# Galaksija_keyboard_matrix.net
KiCad netlist of a schematic drawn in EAGLE
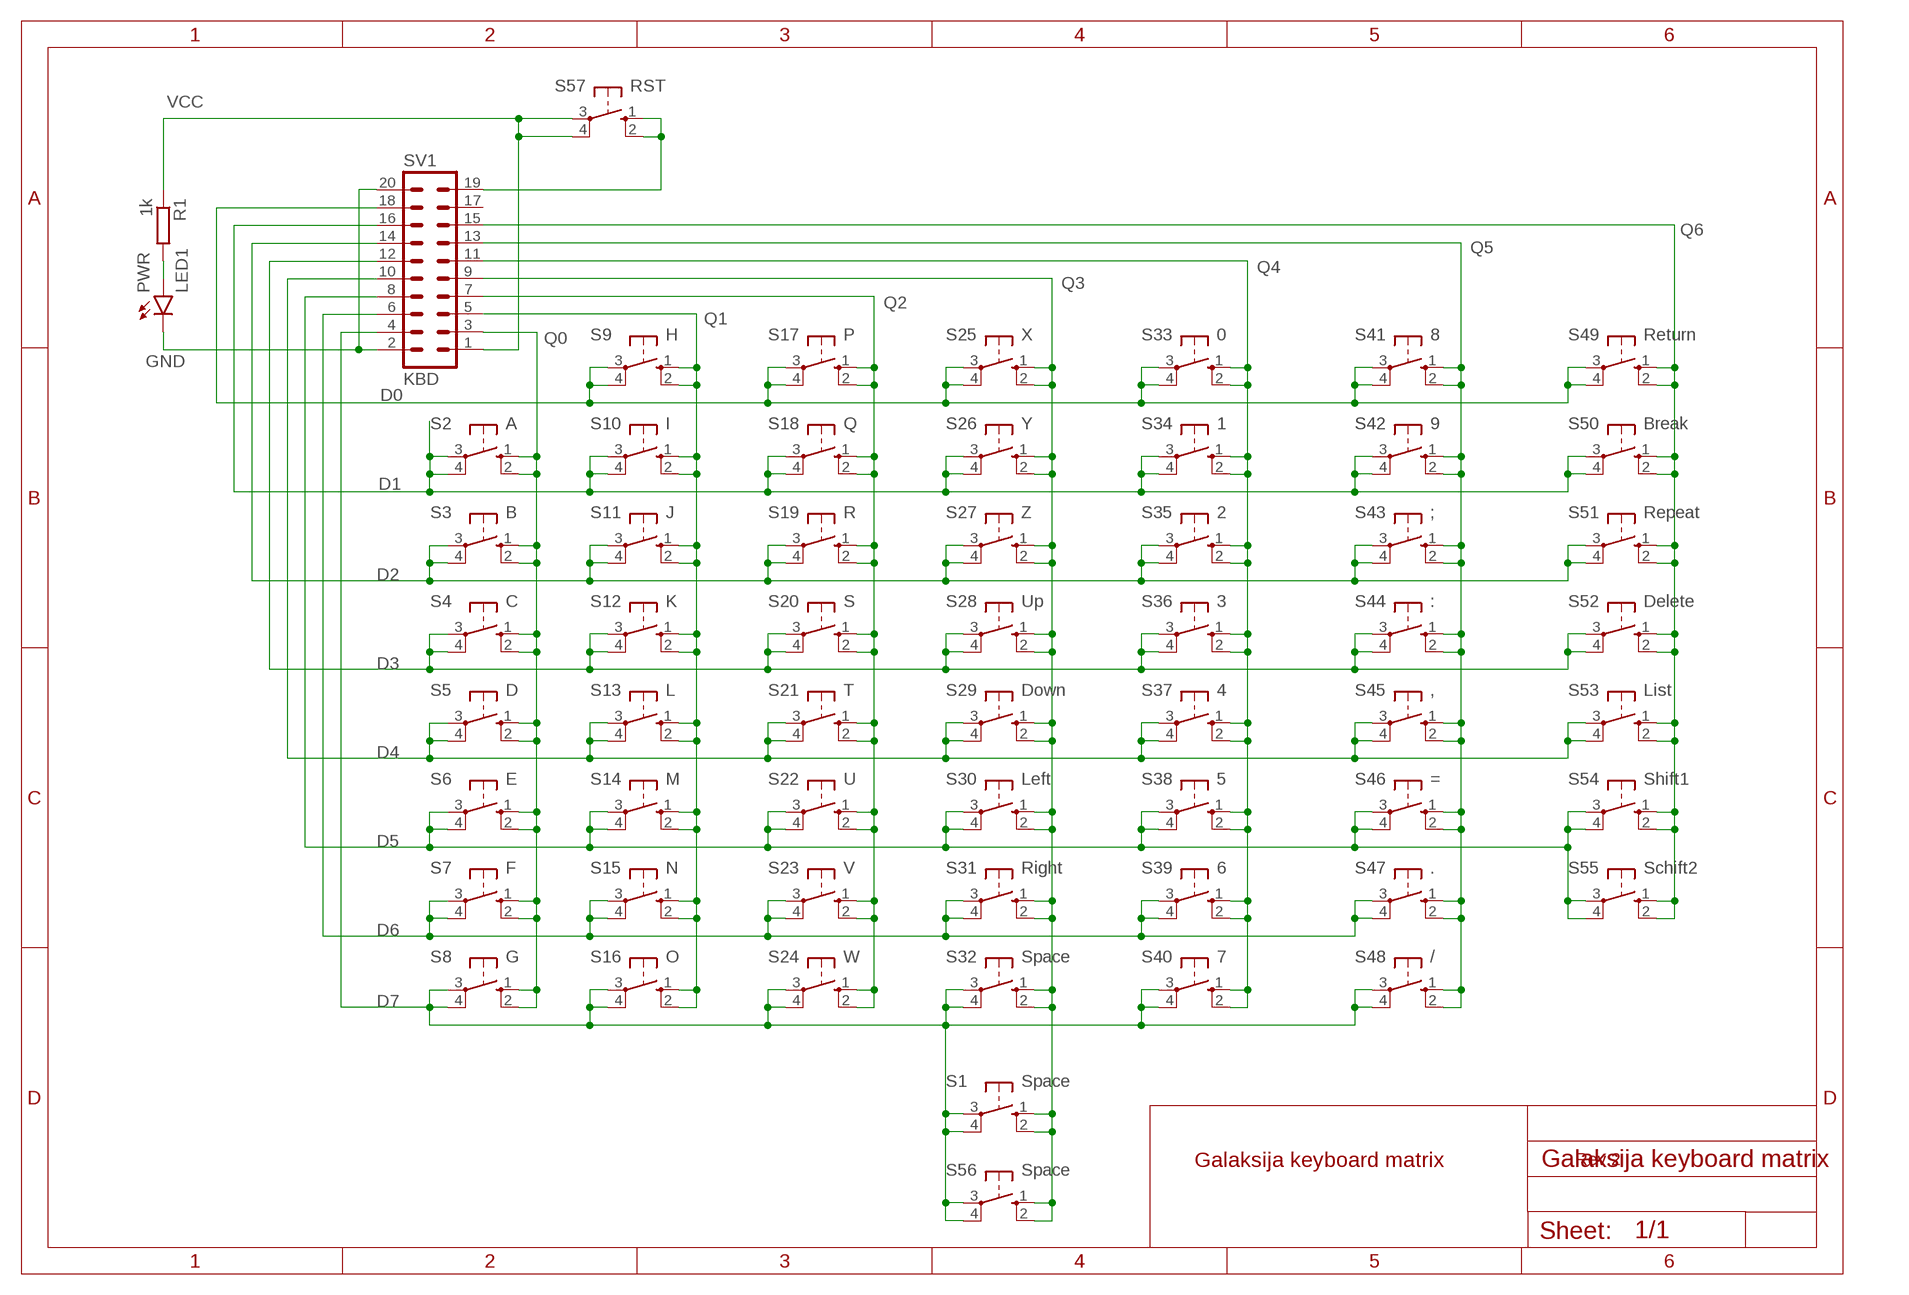
[diagram p0: schematic, sheet 1]

(export (version "E")
  (design (tool "Eeschema 10.0.6"))
  (components
    (comp (ref "LED1")
      (value "PWR")
      (footprint "eagle-import:LED5MM")
      (libsource (lib "eagle-import") (part "LED5MM"))
    )
    (comp (ref "R1")
      (value "1k")
      (footprint "eagle-import:0207_10")
      (libsource (lib "eagle-import") (part "R-EU_0207/10"))
    )
    (comp (ref "S1")
      (value "Space")
      (footprint "eagle-import:B3F-40XX")
      (fields (field (name "MF") "OMRON COMPONENTS USA") (field (name "MPN") "B3F-4000"))
      (libsource (lib "eagle-import") (part "40-XX"))
    )
    (comp (ref "S2")
      (value "A")
      (footprint "eagle-import:B3F-40XX")
      (fields (field (name "MF") "OMRON COMPONENTS USA") (field (name "MPN") "B3F-4000"))
      (libsource (lib "eagle-import") (part "40-XX"))
    )
    (comp (ref "S3")
      (value "B")
      (footprint "eagle-import:B3F-40XX")
      (fields (field (name "MF") "OMRON COMPONENTS USA") (field (name "MPN") "B3F-4000"))
      (libsource (lib "eagle-import") (part "40-XX"))
    )
    (comp (ref "S4")
      (value "C")
      (footprint "eagle-import:B3F-40XX")
      (fields (field (name "MF") "OMRON COMPONENTS USA") (field (name "MPN") "B3F-4000"))
      (libsource (lib "eagle-import") (part "40-XX"))
    )
    (comp (ref "S5")
      (value "D")
      (footprint "eagle-import:B3F-40XX")
      (fields (field (name "MF") "OMRON COMPONENTS USA") (field (name "MPN") "B3F-4000"))
      (libsource (lib "eagle-import") (part "40-XX"))
    )
    (comp (ref "S6")
      (value "E")
      (footprint "eagle-import:B3F-40XX")
      (fields (field (name "MF") "OMRON COMPONENTS USA") (field (name "MPN") "B3F-4000"))
      (libsource (lib "eagle-import") (part "40-XX"))
    )
    (comp (ref "S7")
      (value "F")
      (footprint "eagle-import:B3F-40XX")
      (fields (field (name "MF") "OMRON COMPONENTS USA") (field (name "MPN") "B3F-4000"))
      (libsource (lib "eagle-import") (part "40-XX"))
    )
    (comp (ref "S8")
      (value "G")
      (footprint "eagle-import:B3F-40XX")
      (fields (field (name "MF") "OMRON COMPONENTS USA") (field (name "MPN") "B3F-4000"))
      (libsource (lib "eagle-import") (part "40-XX"))
    )
    (comp (ref "S9")
      (value "H")
      (footprint "eagle-import:B3F-40XX")
      (fields (field (name "MF") "OMRON COMPONENTS USA") (field (name "MPN") "B3F-4000"))
      (libsource (lib "eagle-import") (part "40-XX"))
    )
    (comp (ref "S10")
      (value "I")
      (footprint "eagle-import:B3F-40XX")
      (fields (field (name "MF") "OMRON COMPONENTS USA") (field (name "MPN") "B3F-4000"))
      (libsource (lib "eagle-import") (part "40-XX"))
    )
    (comp (ref "S11")
      (value "J")
      (footprint "eagle-import:B3F-40XX")
      (fields (field (name "MF") "OMRON COMPONENTS USA") (field (name "MPN") "B3F-4000"))
      (libsource (lib "eagle-import") (part "40-XX"))
    )
    (comp (ref "S12")
      (value "K")
      (footprint "eagle-import:B3F-40XX")
      (fields (field (name "MF") "OMRON COMPONENTS USA") (field (name "MPN") "B3F-4000"))
      (libsource (lib "eagle-import") (part "40-XX"))
    )
    (comp (ref "S13")
      (value "L")
      (footprint "eagle-import:B3F-40XX")
      (fields (field (name "MF") "OMRON COMPONENTS USA") (field (name "MPN") "B3F-4000"))
      (libsource (lib "eagle-import") (part "40-XX"))
    )
    (comp (ref "S14")
      (value "M")
      (footprint "eagle-import:B3F-40XX")
      (fields (field (name "MF") "OMRON COMPONENTS USA") (field (name "MPN") "B3F-4000"))
      (libsource (lib "eagle-import") (part "40-XX"))
    )
    (comp (ref "S15")
      (value "N")
      (footprint "eagle-import:B3F-40XX")
      (fields (field (name "MF") "OMRON COMPONENTS USA") (field (name "MPN") "B3F-4000"))
      (libsource (lib "eagle-import") (part "40-XX"))
    )
    (comp (ref "S16")
      (value "O")
      (footprint "eagle-import:B3F-40XX")
      (fields (field (name "MF") "OMRON COMPONENTS USA") (field (name "MPN") "B3F-4000"))
      (libsource (lib "eagle-import") (part "40-XX"))
    )
    (comp (ref "S17")
      (value "P")
      (footprint "eagle-import:B3F-40XX")
      (fields (field (name "MF") "OMRON COMPONENTS USA") (field (name "MPN") "B3F-4000"))
      (libsource (lib "eagle-import") (part "40-XX"))
    )
    (comp (ref "S18")
      (value "Q")
      (footprint "eagle-import:B3F-40XX")
      (fields (field (name "MF") "OMRON COMPONENTS USA") (field (name "MPN") "B3F-4000"))
      (libsource (lib "eagle-import") (part "40-XX"))
    )
    (comp (ref "S19")
      (value "R")
      (footprint "eagle-import:B3F-40XX")
      (fields (field (name "MF") "OMRON COMPONENTS USA") (field (name "MPN") "B3F-4000"))
      (libsource (lib "eagle-import") (part "40-XX"))
    )
    (comp (ref "S20")
      (value "S")
      (footprint "eagle-import:B3F-40XX")
      (fields (field (name "MF") "OMRON COMPONENTS USA") (field (name "MPN") "B3F-4000"))
      (libsource (lib "eagle-import") (part "40-XX"))
    )
    (comp (ref "S21")
      (value "T")
      (footprint "eagle-import:B3F-40XX")
      (fields (field (name "MF") "OMRON COMPONENTS USA") (field (name "MPN") "B3F-4000"))
      (libsource (lib "eagle-import") (part "40-XX"))
    )
    (comp (ref "S22")
      (value "U")
      (footprint "eagle-import:B3F-40XX")
      (fields (field (name "MF") "OMRON COMPONENTS USA") (field (name "MPN") "B3F-4000"))
      (libsource (lib "eagle-import") (part "40-XX"))
    )
    (comp (ref "S23")
      (value "V")
      (footprint "eagle-import:B3F-40XX")
      (fields (field (name "MF") "OMRON COMPONENTS USA") (field (name "MPN") "B3F-4000"))
      (libsource (lib "eagle-import") (part "40-XX"))
    )
    (comp (ref "S24")
      (value "W")
      (footprint "eagle-import:B3F-40XX")
      (fields (field (name "MF") "OMRON COMPONENTS USA") (field (name "MPN") "B3F-4000"))
      (libsource (lib "eagle-import") (part "40-XX"))
    )
    (comp (ref "S25")
      (value "X")
      (footprint "eagle-import:B3F-40XX")
      (fields (field (name "MF") "OMRON COMPONENTS USA") (field (name "MPN") "B3F-4000"))
      (libsource (lib "eagle-import") (part "40-XX"))
    )
    (comp (ref "S26")
      (value "Y")
      (footprint "eagle-import:B3F-40XX")
      (fields (field (name "MF") "OMRON COMPONENTS USA") (field (name "MPN") "B3F-4000"))
      (libsource (lib "eagle-import") (part "40-XX"))
    )
    (comp (ref "S27")
      (value "Z")
      (footprint "eagle-import:B3F-40XX")
      (fields (field (name "MF") "OMRON COMPONENTS USA") (field (name "MPN") "B3F-4000"))
      (libsource (lib "eagle-import") (part "40-XX"))
    )
    (comp (ref "S28")
      (value "Up")
      (footprint "eagle-import:B3F-40XX")
      (fields (field (name "MF") "OMRON COMPONENTS USA") (field (name "MPN") "B3F-4000"))
      (libsource (lib "eagle-import") (part "40-XX"))
    )
    (comp (ref "S29")
      (value "Down")
      (footprint "eagle-import:B3F-40XX")
      (fields (field (name "MF") "OMRON COMPONENTS USA") (field (name "MPN") "B3F-4000"))
      (libsource (lib "eagle-import") (part "40-XX"))
    )
    (comp (ref "S30")
      (value "Left")
      (footprint "eagle-import:B3F-40XX")
      (fields (field (name "MF") "OMRON COMPONENTS USA") (field (name "MPN") "B3F-4000"))
      (libsource (lib "eagle-import") (part "40-XX"))
    )
    (comp (ref "S31")
      (value "Right")
      (footprint "eagle-import:B3F-40XX")
      (fields (field (name "MF") "OMRON COMPONENTS USA") (field (name "MPN") "B3F-4000"))
      (libsource (lib "eagle-import") (part "40-XX"))
    )
    (comp (ref "S32")
      (value "Space")
      (footprint "eagle-import:B3F-40XX")
      (fields (field (name "MF") "OMRON COMPONENTS USA") (field (name "MPN") "B3F-4000"))
      (libsource (lib "eagle-import") (part "40-XX"))
    )
    (comp (ref "S33")
      (value "0")
      (footprint "eagle-import:B3F-40XX")
      (fields (field (name "MF") "OMRON COMPONENTS USA") (field (name "MPN") "B3F-4000"))
      (libsource (lib "eagle-import") (part "40-XX"))
    )
    (comp (ref "S34")
      (value "1")
      (footprint "eagle-import:B3F-40XX")
      (fields (field (name "MF") "OMRON COMPONENTS USA") (field (name "MPN") "B3F-4000"))
      (libsource (lib "eagle-import") (part "40-XX"))
    )
    (comp (ref "S35")
      (value "2")
      (footprint "eagle-import:B3F-40XX")
      (fields (field (name "MF") "OMRON COMPONENTS USA") (field (name "MPN") "B3F-4000"))
      (libsource (lib "eagle-import") (part "40-XX"))
    )
    (comp (ref "S36")
      (value "3")
      (footprint "eagle-import:B3F-40XX")
      (fields (field (name "MF") "OMRON COMPONENTS USA") (field (name "MPN") "B3F-4000"))
      (libsource (lib "eagle-import") (part "40-XX"))
    )
    (comp (ref "S37")
      (value "4")
      (footprint "eagle-import:B3F-40XX")
      (fields (field (name "MF") "OMRON COMPONENTS USA") (field (name "MPN") "B3F-4000"))
      (libsource (lib "eagle-import") (part "40-XX"))
    )
    (comp (ref "S38")
      (value "5")
      (footprint "eagle-import:B3F-40XX")
      (fields (field (name "MF") "OMRON COMPONENTS USA") (field (name "MPN") "B3F-4000"))
      (libsource (lib "eagle-import") (part "40-XX"))
    )
    (comp (ref "S39")
      (value "6")
      (footprint "eagle-import:B3F-40XX")
      (fields (field (name "MF") "OMRON COMPONENTS USA") (field (name "MPN") "B3F-4000"))
      (libsource (lib "eagle-import") (part "40-XX"))
    )
    (comp (ref "S40")
      (value "7")
      (footprint "eagle-import:B3F-40XX")
      (fields (field (name "MF") "OMRON COMPONENTS USA") (field (name "MPN") "B3F-4000"))
      (libsource (lib "eagle-import") (part "40-XX"))
    )
    (comp (ref "S41")
      (value "8")
      (footprint "eagle-import:B3F-40XX")
      (fields (field (name "MF") "OMRON COMPONENTS USA") (field (name "MPN") "B3F-4000"))
      (libsource (lib "eagle-import") (part "40-XX"))
    )
    (comp (ref "S42")
      (value "9")
      (footprint "eagle-import:B3F-40XX")
      (fields (field (name "MF") "OMRON COMPONENTS USA") (field (name "MPN") "B3F-4000"))
      (libsource (lib "eagle-import") (part "40-XX"))
    )
    (comp (ref "S43")
      (value ";")
      (footprint "eagle-import:B3F-40XX")
      (fields (field (name "MF") "OMRON COMPONENTS USA") (field (name "MPN") "B3F-4000"))
      (libsource (lib "eagle-import") (part "40-XX"))
    )
    (comp (ref "S44")
      (value ":")
      (footprint "eagle-import:B3F-40XX")
      (fields (field (name "MF") "OMRON COMPONENTS USA") (field (name "MPN") "B3F-4000"))
      (libsource (lib "eagle-import") (part "40-XX"))
    )
    (comp (ref "S45")
      (value ",")
      (footprint "eagle-import:B3F-40XX")
      (fields (field (name "MF") "OMRON COMPONENTS USA") (field (name "MPN") "B3F-4000"))
      (libsource (lib "eagle-import") (part "40-XX"))
    )
    (comp (ref "S46")
      (value "=")
      (footprint "eagle-import:B3F-40XX")
      (fields (field (name "MF") "OMRON COMPONENTS USA") (field (name "MPN") "B3F-4000"))
      (libsource (lib "eagle-import") (part "40-XX"))
    )
    (comp (ref "S47")
      (value ".")
      (footprint "eagle-import:B3F-40XX")
      (fields (field (name "MF") "OMRON COMPONENTS USA") (field (name "MPN") "B3F-4000"))
      (libsource (lib "eagle-import") (part "40-XX"))
    )
    (comp (ref "S48")
      (value "/")
      (footprint "eagle-import:B3F-40XX")
      (fields (field (name "MF") "OMRON COMPONENTS USA") (field (name "MPN") "B3F-4000"))
      (libsource (lib "eagle-import") (part "40-XX"))
    )
    (comp (ref "S49")
      (value "Return")
      (footprint "eagle-import:B3F-40XX")
      (fields (field (name "MF") "OMRON COMPONENTS USA") (field (name "MPN") "B3F-4000"))
      (libsource (lib "eagle-import") (part "40-XX"))
    )
    (comp (ref "S50")
      (value "Break")
      (footprint "eagle-import:B3F-40XX")
      (fields (field (name "MF") "OMRON COMPONENTS USA") (field (name "MPN") "B3F-4000"))
      (libsource (lib "eagle-import") (part "40-XX"))
    )
    (comp (ref "S51")
      (value "Repeat")
      (footprint "eagle-import:B3F-40XX")
      (fields (field (name "MF") "OMRON COMPONENTS USA") (field (name "MPN") "B3F-4000"))
      (libsource (lib "eagle-import") (part "40-XX"))
    )
    (comp (ref "S52")
      (value "Delete")
      (footprint "eagle-import:B3F-40XX")
      (fields (field (name "MF") "OMRON COMPONENTS USA") (field (name "MPN") "B3F-4000"))
      (libsource (lib "eagle-import") (part "40-XX"))
    )
    (comp (ref "S53")
      (value "List")
      (footprint "eagle-import:B3F-40XX")
      (fields (field (name "MF") "OMRON COMPONENTS USA") (field (name "MPN") "B3F-4000"))
      (libsource (lib "eagle-import") (part "40-XX"))
    )
    (comp (ref "S54")
      (value "Shift1")
      (footprint "eagle-import:B3F-40XX")
      (fields (field (name "MF") "OMRON COMPONENTS USA") (field (name "MPN") "B3F-4000"))
      (libsource (lib "eagle-import") (part "40-XX"))
    )
    (comp (ref "S55")
      (value "Schift2")
      (footprint "eagle-import:B3F-40XX")
      (fields (field (name "MF") "OMRON COMPONENTS USA") (field (name "MPN") "B3F-4000"))
      (libsource (lib "eagle-import") (part "40-XX"))
    )
    (comp (ref "S56")
      (value "Space")
      (footprint "eagle-import:B3F-40XX")
      (fields (field (name "MF") "OMRON COMPONENTS USA") (field (name "MPN") "B3F-4000"))
      (libsource (lib "eagle-import") (part "40-XX"))
    )
    (comp (ref "S57")
      (value "RST")
      (footprint "eagle-import:B3F-40XX")
      (fields (field (name "MF") "OMRON COMPONENTS USA") (field (name "MPN") "B3F-4000"))
      (libsource (lib "eagle-import") (part "40-XX"))
    )
    (comp (ref "SV1")
      (value "KBD")
      (footprint "eagle-import:ML20")
      (libsource (lib "eagle-import") (part "ML20"))
    )
  )
  (nets
    (net (code "1") (name "/D0") (class "Default")
      (node (ref "S17") (pin "3") (pinfunction "P_3") (pintype "passive"))
      (node (ref "S17") (pin "4") (pinfunction "P1_4") (pintype "passive"))
      (node (ref "S25") (pin "3") (pinfunction "P_3") (pintype "passive"))
      (node (ref "S25") (pin "4") (pinfunction "P1_4") (pintype "passive"))
      (node (ref "S33") (pin "3") (pinfunction "P_3") (pintype "passive"))
      (node (ref "S33") (pin "4") (pinfunction "P1_4") (pintype "passive"))
      (node (ref "S41") (pin "3") (pinfunction "P_3") (pintype "passive"))
      (node (ref "S41") (pin "4") (pinfunction "P1_4") (pintype "passive"))
      (node (ref "S49") (pin "3") (pinfunction "P_3") (pintype "passive"))
      (node (ref "S49") (pin "4") (pinfunction "P1_4") (pintype "passive"))
      (node (ref "S9") (pin "3") (pinfunction "P_3") (pintype "passive"))
      (node (ref "S9") (pin "4") (pinfunction "P1_4") (pintype "passive"))
      (node (ref "SV1") (pin "18") (pinfunction "18_18") (pintype "passive"))
    )
    (net (code "2") (name "/D1") (class "Default")
      (node (ref "S10") (pin "3") (pinfunction "P_3") (pintype "passive"))
      (node (ref "S10") (pin "4") (pinfunction "P1_4") (pintype "passive"))
      (node (ref "S18") (pin "3") (pinfunction "P_3") (pintype "passive"))
      (node (ref "S18") (pin "4") (pinfunction "P1_4") (pintype "passive"))
      (node (ref "S2") (pin "3") (pinfunction "P_3") (pintype "passive"))
      (node (ref "S2") (pin "4") (pinfunction "P1_4") (pintype "passive"))
      (node (ref "S26") (pin "3") (pinfunction "P_3") (pintype "passive"))
      (node (ref "S26") (pin "4") (pinfunction "P1_4") (pintype "passive"))
      (node (ref "S34") (pin "3") (pinfunction "P_3") (pintype "passive"))
      (node (ref "S34") (pin "4") (pinfunction "P1_4") (pintype "passive"))
      (node (ref "S42") (pin "3") (pinfunction "P_3") (pintype "passive"))
      (node (ref "S42") (pin "4") (pinfunction "P1_4") (pintype "passive"))
      (node (ref "S50") (pin "3") (pinfunction "P_3") (pintype "passive"))
      (node (ref "S50") (pin "4") (pinfunction "P1_4") (pintype "passive"))
      (node (ref "SV1") (pin "16") (pinfunction "16_16") (pintype "passive"))
    )
    (net (code "3") (name "/D2") (class "Default")
      (node (ref "S11") (pin "3") (pinfunction "P_3") (pintype "passive"))
      (node (ref "S11") (pin "4") (pinfunction "P1_4") (pintype "passive"))
      (node (ref "S19") (pin "3") (pinfunction "P_3") (pintype "passive"))
      (node (ref "S19") (pin "4") (pinfunction "P1_4") (pintype "passive"))
      (node (ref "S27") (pin "3") (pinfunction "P_3") (pintype "passive"))
      (node (ref "S27") (pin "4") (pinfunction "P1_4") (pintype "passive"))
      (node (ref "S3") (pin "3") (pinfunction "P_3") (pintype "passive"))
      (node (ref "S3") (pin "4") (pinfunction "P1_4") (pintype "passive"))
      (node (ref "S35") (pin "3") (pinfunction "P_3") (pintype "passive"))
      (node (ref "S35") (pin "4") (pinfunction "P1_4") (pintype "passive"))
      (node (ref "S43") (pin "3") (pinfunction "P_3") (pintype "passive"))
      (node (ref "S43") (pin "4") (pinfunction "P1_4") (pintype "passive"))
      (node (ref "S51") (pin "3") (pinfunction "P_3") (pintype "passive"))
      (node (ref "S51") (pin "4") (pinfunction "P1_4") (pintype "passive"))
      (node (ref "SV1") (pin "14") (pinfunction "14_14") (pintype "passive"))
    )
    (net (code "4") (name "/D3") (class "Default")
      (node (ref "S12") (pin "3") (pinfunction "P_3") (pintype "passive"))
      (node (ref "S12") (pin "4") (pinfunction "P1_4") (pintype "passive"))
      (node (ref "S20") (pin "3") (pinfunction "P_3") (pintype "passive"))
      (node (ref "S20") (pin "4") (pinfunction "P1_4") (pintype "passive"))
      (node (ref "S28") (pin "3") (pinfunction "P_3") (pintype "passive"))
      (node (ref "S28") (pin "4") (pinfunction "P1_4") (pintype "passive"))
      (node (ref "S36") (pin "3") (pinfunction "P_3") (pintype "passive"))
      (node (ref "S36") (pin "4") (pinfunction "P1_4") (pintype "passive"))
      (node (ref "S4") (pin "3") (pinfunction "P_3") (pintype "passive"))
      (node (ref "S4") (pin "4") (pinfunction "P1_4") (pintype "passive"))
      (node (ref "S44") (pin "3") (pinfunction "P_3") (pintype "passive"))
      (node (ref "S44") (pin "4") (pinfunction "P1_4") (pintype "passive"))
      (node (ref "S52") (pin "3") (pinfunction "P_3") (pintype "passive"))
      (node (ref "S52") (pin "4") (pinfunction "P1_4") (pintype "passive"))
      (node (ref "SV1") (pin "12") (pinfunction "12_12") (pintype "passive"))
    )
    (net (code "5") (name "/D4") (class "Default")
      (node (ref "S13") (pin "3") (pinfunction "P_3") (pintype "passive"))
      (node (ref "S13") (pin "4") (pinfunction "P1_4") (pintype "passive"))
      (node (ref "S21") (pin "3") (pinfunction "P_3") (pintype "passive"))
      (node (ref "S21") (pin "4") (pinfunction "P1_4") (pintype "passive"))
      (node (ref "S29") (pin "3") (pinfunction "P_3") (pintype "passive"))
      (node (ref "S29") (pin "4") (pinfunction "P1_4") (pintype "passive"))
      (node (ref "S37") (pin "3") (pinfunction "P_3") (pintype "passive"))
      (node (ref "S37") (pin "4") (pinfunction "P1_4") (pintype "passive"))
      (node (ref "S45") (pin "3") (pinfunction "P_3") (pintype "passive"))
      (node (ref "S45") (pin "4") (pinfunction "P1_4") (pintype "passive"))
      (node (ref "S5") (pin "3") (pinfunction "P_3") (pintype "passive"))
      (node (ref "S5") (pin "4") (pinfunction "P1_4") (pintype "passive"))
      (node (ref "S53") (pin "3") (pinfunction "P_3") (pintype "passive"))
      (node (ref "S53") (pin "4") (pinfunction "P1_4") (pintype "passive"))
      (node (ref "SV1") (pin "10") (pinfunction "10_10") (pintype "passive"))
    )
    (net (code "6") (name "/D5") (class "Default")
      (node (ref "S14") (pin "3") (pinfunction "P_3") (pintype "passive"))
      (node (ref "S14") (pin "4") (pinfunction "P1_4") (pintype "passive"))
      (node (ref "S22") (pin "3") (pinfunction "P_3") (pintype "passive"))
      (node (ref "S22") (pin "4") (pinfunction "P1_4") (pintype "passive"))
      (node (ref "S30") (pin "3") (pinfunction "P_3") (pintype "passive"))
      (node (ref "S30") (pin "4") (pinfunction "P1_4") (pintype "passive"))
      (node (ref "S38") (pin "3") (pinfunction "P_3") (pintype "passive"))
      (node (ref "S38") (pin "4") (pinfunction "P1_4") (pintype "passive"))
      (node (ref "S46") (pin "3") (pinfunction "P_3") (pintype "passive"))
      (node (ref "S46") (pin "4") (pinfunction "P1_4") (pintype "passive"))
      (node (ref "S54") (pin "3") (pinfunction "P_3") (pintype "passive"))
      (node (ref "S54") (pin "4") (pinfunction "P1_4") (pintype "passive"))
      (node (ref "S55") (pin "3") (pinfunction "P_3") (pintype "passive"))
      (node (ref "S55") (pin "4") (pinfunction "P1_4") (pintype "passive"))
      (node (ref "S6") (pin "3") (pinfunction "P_3") (pintype "passive"))
      (node (ref "S6") (pin "4") (pinfunction "P1_4") (pintype "passive"))
      (node (ref "SV1") (pin "8") (pinfunction "8_8") (pintype "passive"))
    )
    (net (code "7") (name "/D6") (class "Default")
      (node (ref "S15") (pin "3") (pinfunction "P_3") (pintype "passive"))
      (node (ref "S15") (pin "4") (pinfunction "P1_4") (pintype "passive"))
      (node (ref "S23") (pin "3") (pinfunction "P_3") (pintype "passive"))
      (node (ref "S23") (pin "4") (pinfunction "P1_4") (pintype "passive"))
      (node (ref "S31") (pin "3") (pinfunction "P_3") (pintype "passive"))
      (node (ref "S31") (pin "4") (pinfunction "P1_4") (pintype "passive"))
      (node (ref "S39") (pin "3") (pinfunction "P_3") (pintype "passive"))
      (node (ref "S39") (pin "4") (pinfunction "P1_4") (pintype "passive"))
      (node (ref "S47") (pin "3") (pinfunction "P_3") (pintype "passive"))
      (node (ref "S47") (pin "4") (pinfunction "P1_4") (pintype "passive"))
      (node (ref "S7") (pin "3") (pinfunction "P_3") (pintype "passive"))
      (node (ref "S7") (pin "4") (pinfunction "P1_4") (pintype "passive"))
      (node (ref "SV1") (pin "6") (pinfunction "6_6") (pintype "passive"))
    )
    (net (code "8") (name "/D7") (class "Default")
      (node (ref "S1") (pin "3") (pinfunction "P_3") (pintype "passive"))
      (node (ref "S1") (pin "4") (pinfunction "P1_4") (pintype "passive"))
      (node (ref "S16") (pin "3") (pinfunction "P_3") (pintype "passive"))
      (node (ref "S16") (pin "4") (pinfunction "P1_4") (pintype "passive"))
      (node (ref "S24") (pin "3") (pinfunction "P_3") (pintype "passive"))
      (node (ref "S24") (pin "4") (pinfunction "P1_4") (pintype "passive"))
      (node (ref "S32") (pin "3") (pinfunction "P_3") (pintype "passive"))
      (node (ref "S32") (pin "4") (pinfunction "P1_4") (pintype "passive"))
      (node (ref "S40") (pin "3") (pinfunction "P_3") (pintype "passive"))
      (node (ref "S40") (pin "4") (pinfunction "P1_4") (pintype "passive"))
      (node (ref "S48") (pin "3") (pinfunction "P_3") (pintype "passive"))
      (node (ref "S48") (pin "4") (pinfunction "P1_4") (pintype "passive"))
      (node (ref "S56") (pin "3") (pinfunction "P_3") (pintype "passive"))
      (node (ref "S56") (pin "4") (pinfunction "P1_4") (pintype "passive"))
      (node (ref "S8") (pin "3") (pinfunction "P_3") (pintype "passive"))
      (node (ref "S8") (pin "4") (pinfunction "P1_4") (pintype "passive"))
      (node (ref "SV1") (pin "4") (pinfunction "4_4") (pintype "passive"))
    )
    (net (code "9") (name "/GND") (class "Default")
      (node (ref "LED1") (pin "K") (pinfunction "C_K") (pintype "passive"))
      (node (ref "SV1") (pin "2") (pinfunction "2_2") (pintype "passive"))
      (node (ref "SV1") (pin "20") (pinfunction "20_20") (pintype "passive"))
    )
    (net (code "10") (name "/Q0") (class "Default")
      (node (ref "S2") (pin "1") (pinfunction "S_1") (pintype "passive"))
      (node (ref "S2") (pin "2") (pinfunction "S1_2") (pintype "passive"))
      (node (ref "S3") (pin "1") (pinfunction "S_1") (pintype "passive"))
      (node (ref "S3") (pin "2") (pinfunction "S1_2") (pintype "passive"))
      (node (ref "S4") (pin "1") (pinfunction "S_1") (pintype "passive"))
      (node (ref "S4") (pin "2") (pinfunction "S1_2") (pintype "passive"))
      (node (ref "S5") (pin "1") (pinfunction "S_1") (pintype "passive"))
      (node (ref "S5") (pin "2") (pinfunction "S1_2") (pintype "passive"))
      (node (ref "S6") (pin "1") (pinfunction "S_1") (pintype "passive"))
      (node (ref "S6") (pin "2") (pinfunction "S1_2") (pintype "passive"))
      (node (ref "S7") (pin "1") (pinfunction "S_1") (pintype "passive"))
      (node (ref "S7") (pin "2") (pinfunction "S1_2") (pintype "passive"))
      (node (ref "S8") (pin "1") (pinfunction "S_1") (pintype "passive"))
      (node (ref "S8") (pin "2") (pinfunction "S1_2") (pintype "passive"))
      (node (ref "SV1") (pin "3") (pinfunction "3_3") (pintype "passive"))
    )
    (net (code "11") (name "/Q1") (class "Default")
      (node (ref "S10") (pin "1") (pinfunction "S_1") (pintype "passive"))
      (node (ref "S10") (pin "2") (pinfunction "S1_2") (pintype "passive"))
      (node (ref "S11") (pin "1") (pinfunction "S_1") (pintype "passive"))
      (node (ref "S11") (pin "2") (pinfunction "S1_2") (pintype "passive"))
      (node (ref "S12") (pin "1") (pinfunction "S_1") (pintype "passive"))
      (node (ref "S12") (pin "2") (pinfunction "S1_2") (pintype "passive"))
      (node (ref "S13") (pin "1") (pinfunction "S_1") (pintype "passive"))
      (node (ref "S13") (pin "2") (pinfunction "S1_2") (pintype "passive"))
      (node (ref "S14") (pin "1") (pinfunction "S_1") (pintype "passive"))
      (node (ref "S14") (pin "2") (pinfunction "S1_2") (pintype "passive"))
      (node (ref "S15") (pin "1") (pinfunction "S_1") (pintype "passive"))
      (node (ref "S15") (pin "2") (pinfunction "S1_2") (pintype "passive"))
      (node (ref "S16") (pin "1") (pinfunction "S_1") (pintype "passive"))
      (node (ref "S16") (pin "2") (pinfunction "S1_2") (pintype "passive"))
      (node (ref "S9") (pin "1") (pinfunction "S_1") (pintype "passive"))
      (node (ref "S9") (pin "2") (pinfunction "S1_2") (pintype "passive"))
      (node (ref "SV1") (pin "5") (pinfunction "5_5") (pintype "passive"))
    )
    (net (code "12") (name "/Q2") (class "Default")
      (node (ref "S17") (pin "1") (pinfunction "S_1") (pintype "passive"))
      (node (ref "S17") (pin "2") (pinfunction "S1_2") (pintype "passive"))
      (node (ref "S18") (pin "1") (pinfunction "S_1") (pintype "passive"))
      (node (ref "S18") (pin "2") (pinfunction "S1_2") (pintype "passive"))
      (node (ref "S19") (pin "1") (pinfunction "S_1") (pintype "passive"))
      (node (ref "S19") (pin "2") (pinfunction "S1_2") (pintype "passive"))
      (node (ref "S20") (pin "1") (pinfunction "S_1") (pintype "passive"))
      (node (ref "S20") (pin "2") (pinfunction "S1_2") (pintype "passive"))
      (node (ref "S21") (pin "1") (pinfunction "S_1") (pintype "passive"))
      (node (ref "S21") (pin "2") (pinfunction "S1_2") (pintype "passive"))
      (node (ref "S22") (pin "1") (pinfunction "S_1") (pintype "passive"))
      (node (ref "S22") (pin "2") (pinfunction "S1_2") (pintype "passive"))
      (node (ref "S23") (pin "1") (pinfunction "S_1") (pintype "passive"))
      (node (ref "S23") (pin "2") (pinfunction "S1_2") (pintype "passive"))
      (node (ref "S24") (pin "1") (pinfunction "S_1") (pintype "passive"))
      (node (ref "S24") (pin "2") (pinfunction "S1_2") (pintype "passive"))
      (node (ref "SV1") (pin "7") (pinfunction "7_7") (pintype "passive"))
    )
    (net (code "13") (name "/Q3") (class "Default")
      (node (ref "S1") (pin "1") (pinfunction "S_1") (pintype "passive"))
      (node (ref "S1") (pin "2") (pinfunction "S1_2") (pintype "passive"))
      (node (ref "S25") (pin "1") (pinfunction "S_1") (pintype "passive"))
      (node (ref "S25") (pin "2") (pinfunction "S1_2") (pintype "passive"))
      (node (ref "S26") (pin "1") (pinfunction "S_1") (pintype "passive"))
      (node (ref "S26") (pin "2") (pinfunction "S1_2") (pintype "passive"))
      (node (ref "S27") (pin "1") (pinfunction "S_1") (pintype "passive"))
      (node (ref "S27") (pin "2") (pinfunction "S1_2") (pintype "passive"))
      (node (ref "S28") (pin "1") (pinfunction "S_1") (pintype "passive"))
      (node (ref "S28") (pin "2") (pinfunction "S1_2") (pintype "passive"))
      (node (ref "S29") (pin "1") (pinfunction "S_1") (pintype "passive"))
      (node (ref "S29") (pin "2") (pinfunction "S1_2") (pintype "passive"))
      (node (ref "S30") (pin "1") (pinfunction "S_1") (pintype "passive"))
      (node (ref "S30") (pin "2") (pinfunction "S1_2") (pintype "passive"))
      (node (ref "S31") (pin "1") (pinfunction "S_1") (pintype "passive"))
      (node (ref "S31") (pin "2") (pinfunction "S1_2") (pintype "passive"))
      (node (ref "S32") (pin "1") (pinfunction "S_1") (pintype "passive"))
      (node (ref "S32") (pin "2") (pinfunction "S1_2") (pintype "passive"))
      (node (ref "S56") (pin "1") (pinfunction "S_1") (pintype "passive"))
      (node (ref "S56") (pin "2") (pinfunction "S1_2") (pintype "passive"))
      (node (ref "SV1") (pin "9") (pinfunction "9_9") (pintype "passive"))
    )
    (net (code "14") (name "/Q4") (class "Default")
      (node (ref "S33") (pin "1") (pinfunction "S_1") (pintype "passive"))
      (node (ref "S33") (pin "2") (pinfunction "S1_2") (pintype "passive"))
      (node (ref "S34") (pin "1") (pinfunction "S_1") (pintype "passive"))
      (node (ref "S34") (pin "2") (pinfunction "S1_2") (pintype "passive"))
      (node (ref "S35") (pin "1") (pinfunction "S_1") (pintype "passive"))
      (node (ref "S35") (pin "2") (pinfunction "S1_2") (pintype "passive"))
      (node (ref "S36") (pin "1") (pinfunction "S_1") (pintype "passive"))
      (node (ref "S36") (pin "2") (pinfunction "S1_2") (pintype "passive"))
      (node (ref "S37") (pin "1") (pinfunction "S_1") (pintype "passive"))
      (node (ref "S37") (pin "2") (pinfunction "S1_2") (pintype "passive"))
      (node (ref "S38") (pin "1") (pinfunction "S_1") (pintype "passive"))
      (node (ref "S38") (pin "2") (pinfunction "S1_2") (pintype "passive"))
      (node (ref "S39") (pin "1") (pinfunction "S_1") (pintype "passive"))
      (node (ref "S39") (pin "2") (pinfunction "S1_2") (pintype "passive"))
      (node (ref "S40") (pin "1") (pinfunction "S_1") (pintype "passive"))
      (node (ref "S40") (pin "2") (pinfunction "S1_2") (pintype "passive"))
      (node (ref "SV1") (pin "11") (pinfunction "11_11") (pintype "passive"))
    )
    (net (code "15") (name "/Q5") (class "Default")
      (node (ref "S41") (pin "1") (pinfunction "S_1") (pintype "passive"))
      (node (ref "S41") (pin "2") (pinfunction "S1_2") (pintype "passive"))
      (node (ref "S42") (pin "1") (pinfunction "S_1") (pintype "passive"))
      (node (ref "S42") (pin "2") (pinfunction "S1_2") (pintype "passive"))
      (node (ref "S43") (pin "1") (pinfunction "S_1") (pintype "passive"))
      (node (ref "S43") (pin "2") (pinfunction "S1_2") (pintype "passive"))
      (node (ref "S44") (pin "1") (pinfunction "S_1") (pintype "passive"))
      (node (ref "S44") (pin "2") (pinfunction "S1_2") (pintype "passive"))
      (node (ref "S45") (pin "1") (pinfunction "S_1") (pintype "passive"))
      (node (ref "S45") (pin "2") (pinfunction "S1_2") (pintype "passive"))
      (node (ref "S46") (pin "1") (pinfunction "S_1") (pintype "passive"))
      (node (ref "S46") (pin "2") (pinfunction "S1_2") (pintype "passive"))
      (node (ref "S47") (pin "1") (pinfunction "S_1") (pintype "passive"))
      (node (ref "S47") (pin "2") (pinfunction "S1_2") (pintype "passive"))
      (node (ref "S48") (pin "1") (pinfunction "S_1") (pintype "passive"))
      (node (ref "S48") (pin "2") (pinfunction "S1_2") (pintype "passive"))
      (node (ref "SV1") (pin "13") (pinfunction "13_13") (pintype "passive"))
    )
    (net (code "16") (name "/Q6") (class "Default")
      (node (ref "S49") (pin "1") (pinfunction "S_1") (pintype "passive"))
      (node (ref "S49") (pin "2") (pinfunction "S1_2") (pintype "passive"))
      (node (ref "S50") (pin "1") (pinfunction "S_1") (pintype "passive"))
      (node (ref "S50") (pin "2") (pinfunction "S1_2") (pintype "passive"))
      (node (ref "S51") (pin "1") (pinfunction "S_1") (pintype "passive"))
      (node (ref "S51") (pin "2") (pinfunction "S1_2") (pintype "passive"))
      (node (ref "S52") (pin "1") (pinfunction "S_1") (pintype "passive"))
      (node (ref "S52") (pin "2") (pinfunction "S1_2") (pintype "passive"))
      (node (ref "S53") (pin "1") (pinfunction "S_1") (pintype "passive"))
      (node (ref "S53") (pin "2") (pinfunction "S1_2") (pintype "passive"))
      (node (ref "S54") (pin "1") (pinfunction "S_1") (pintype "passive"))
      (node (ref "S54") (pin "2") (pinfunction "S1_2") (pintype "passive"))
      (node (ref "S55") (pin "1") (pinfunction "S_1") (pintype "passive"))
      (node (ref "S55") (pin "2") (pinfunction "S1_2") (pintype "passive"))
      (node (ref "SV1") (pin "15") (pinfunction "15_15") (pintype "passive"))
    )
    (net (code "17") (name "/VCC") (class "Default")
      (node (ref "R1") (pin "1") (pinfunction "1_1") (pintype "passive"))
      (node (ref "S57") (pin "3") (pinfunction "P_3") (pintype "passive"))
      (node (ref "S57") (pin "4") (pinfunction "P1_4") (pintype "passive"))
      (node (ref "SV1") (pin "1") (pinfunction "1_1") (pintype "passive"))
    )
    (net (code "18") (name "Net-(LED1-PadA)") (class "Default")
      (node (ref "LED1") (pin "A") (pinfunction "A_A") (pintype "passive"))
      (node (ref "R1") (pin "2") (pinfunction "2_2") (pintype "passive"))
    )
    (net (code "19") (name "Net-(S57-S)") (class "Default")
      (node (ref "S57") (pin "1") (pinfunction "S_1") (pintype "passive"))
      (node (ref "S57") (pin "2") (pinfunction "S1_2") (pintype "passive"))
      (node (ref "SV1") (pin "19") (pinfunction "19_19") (pintype "passive"))
    )
    (net (code "20") (name "unconnected-(SV1-Pad17)") (class "Default")
      (node (ref "SV1") (pin "17") (pinfunction "17_17") (pintype "passive"))
    )
  )
)
